# LF3.net
KiCad netlist of a schematic drawn in EasyEDA Pro
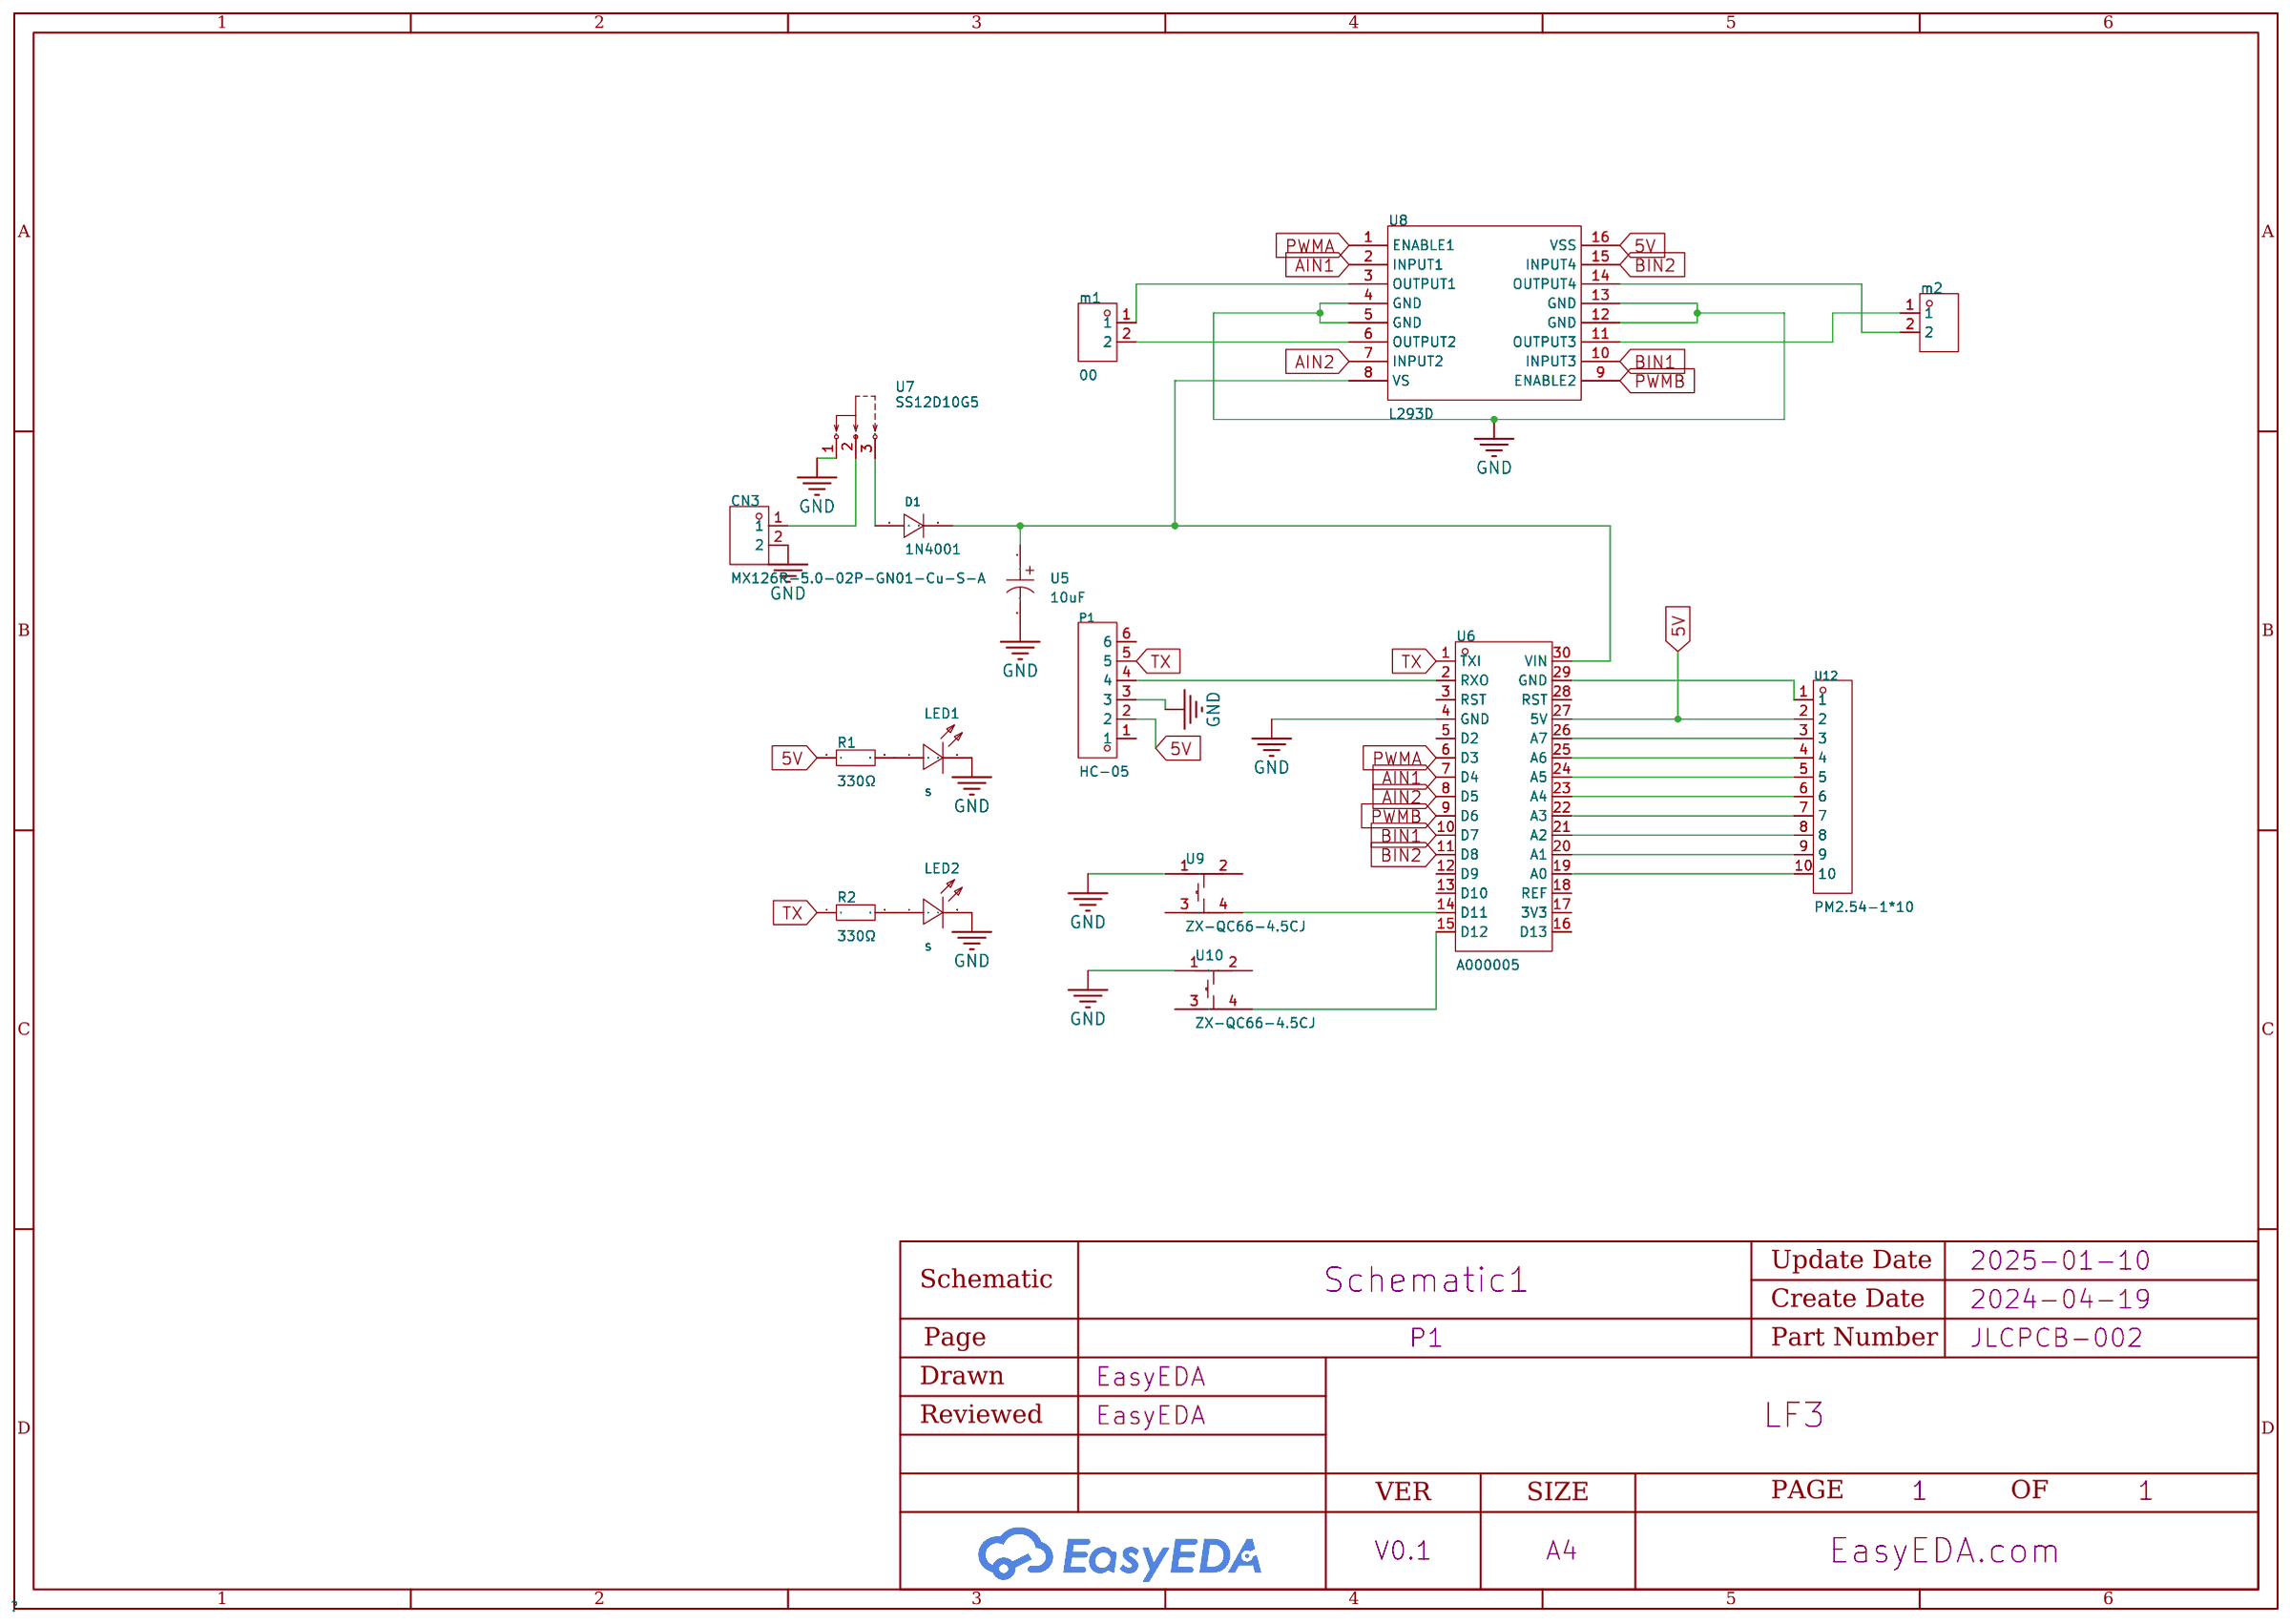
[diagram p0: schematic sheet]

(export (version "E")
  (design (tool "Eeschema 10.0.6"))
  (components
    (comp (ref "CN3")
      (value "MX126R-5.0-02P-GN01-Cu-S-A")
      (footprint "easyedapro:CONN-TH_2P-P5.00-L10.0-W10.3")
      (fields (field (name "Manufacturer") "MAX(迈旭)"))
      (libsource (lib "easyedapro") (part "MX126R-5.0-GN01-2P-CU-S-A"))
    )
    (comp (ref "D1")
      (value "1N4001")
      (footprint "easyedapro:DO-41_BD2.4-L4.7-P8.70-D0.9-RD")
      (fields (field (name "Manufacturer") "DIOFIT(對餘科技)"))
      (libsource (lib "easyedapro") (part "1N4001-C169150"))
    )
    (comp (ref "LED1")
      (value "s")
      (footprint "easyedapro:LED-TH_BD3.8-P2.54-FD")
      (fields (field (name "Manufacturer") "TOGIALED(统佳)"))
      (libsource (lib "easyedapro") (part "TJ-L3FYTLDRMFCSFLC2R-A5"))
    )
    (comp (ref "LED2")
      (value "s")
      (footprint "easyedapro:LED-TH_BD3.8-P2.54-FD")
      (fields (field (name "Manufacturer") "TOGIALED(统佳)"))
      (libsource (lib "easyedapro") (part "TJ-L3FYTLDRMFCSFLC2R-A5"))
    )
    (comp (ref "m1")
      (value "00")
      (footprint "easyedapro:CONN-TH_2P-P5.00-L10.0-W10.3")
      (fields (field (name "Manufacturer") "MAX(迈旭)"))
      (libsource (lib "easyedapro") (part "MX126R-5.0-GN01-2P-CU-S-A"))
    )
    (comp (ref "m2")
      (value "MX126R-5.0-02P-GN01-Cu-S-A")
      (footprint "easyedapro:CONN-TH_2P-P5.00-L10.0-W10.3")
      (fields (field (name "Manufacturer") "MAX(迈旭)"))
      (libsource (lib "easyedapro") (part "MX126R-5.0-GN01-2P-CU-S-A"))
    )
    (comp (ref "P1")
      (value "HC-05")
      (footprint "easyedapro:HDR-TH_6P-P2.54-V-F")
      (fields (field (name "Manufacturer") "BOOMELE(博穆精密)"))
      (libsource (lib "easyedapro") (part "Header-Female-2.54_1x6"))
    )
    (comp (ref "R1")
      (value "330Ω")
      (footprint "easyedapro:RES-TH_BD1.9-L3.3-P7.30-D0.5")
      (fields (field (name "Manufacturer Part") "RN16T25800F") (field (name "Manufacturer") "大毅科技"))
      (libsource (lib "easyedapro") (part "RN16T25800F"))
    )
    (comp (ref "R2")
      (value "330Ω")
      (footprint "easyedapro:RES-TH_BD1.9-L3.3-P7.30-D0.5")
      (fields (field (name "Manufacturer Part") "RN16T25800F") (field (name "Manufacturer") "大毅科技"))
      (libsource (lib "easyedapro") (part "RN16T25800F"))
    )
    (comp (ref "U5")
      (value "10uF")
      (footprint "easyedapro:CAP-TH_BD5.0-P2.00-D0.5-FD")
      (fields (field (name "Manufacturer Part") "152EC0400") (field (name "Manufacturer") "KNSCHA(科尼盛)"))
      (libsource (lib "easyedapro") (part "152EC0400"))
    )
    (comp (ref "U6")
      (value "A000005")
      (footprint "easyedapro:COMM-TH_A000005")
      (fields (field (name "Manufacturer") "arduino"))
      (libsource (lib "easyedapro") (part "A000005"))
    )
    (comp (ref "U7")
      (value "SS12D10G5")
      (footprint "easyedapro:SW-TH_SHOU-HAN_SS12D10G4")
      (fields (field (name "Manufacturer") "SHOU HAN(首韩)"))
      (libsource (lib "easyedapro") (part "SS12D10G5"))
    )
    (comp (ref "U8")
      (value "L293D")
      (footprint "easyedapro:DIP-16_L20.0-W6.4-P2.54-LS7.6-BL")
      (fields (field (name "Manufacturer") "ST(意法半导体)"))
      (libsource (lib "easyedapro") (part "L293D"))
    )
    (comp (ref "U9")
      (value "ZX-QC66-4.5CJ")
      (footprint "easyedapro:KEY-TH_4P-L6.0-W6.0-P4.50-LS6.50")
      (fields (field (name "Manufacturer") "Megastar(兆星)"))
      (libsource (lib "easyedapro") (part "ZX-QC66-4.5CJ"))
    )
    (comp (ref "U10")
      (value "ZX-QC66-4.5CJ")
      (footprint "easyedapro:KEY-TH_4P-L6.0-W6.0-P4.50-LS6.50")
      (fields (field (name "Manufacturer") "Megastar(兆星)"))
      (libsource (lib "easyedapro") (part "ZX-QC66-4.5CJ"))
    )
    (comp (ref "U12")
      (value "PM2.54-1*10")
      (footprint "easyedapro:HDR-TH_10P-P2.54-V-F")
      (fields (field (name "Manufacturer") "ZHOURI(洲日)"))
      (libsource (lib "easyedapro") (part "PM2.54-1*10"))
    )
  )
  (nets
    (net (code "1") (name "5V") (class "Default")
      (node (ref "P1") (pin "2") (pinfunction "2_2") (pintype "input"))
      (node (ref "R1") (pin "1") (pinfunction "1_1") (pintype "unspecified"))
      (node (ref "U12") (pin "2") (pinfunction "2_2") (pintype "input"))
      (node (ref "U6") (pin "27") (pinfunction "5V_27") (pintype "unspecified"))
      (node (ref "U8") (pin "16") (pinfunction "VSS_16") (pintype "unspecified"))
    )
    (net (code "2") (name "AIN1") (class "Default")
      (node (ref "U6") (pin "7") (pinfunction "D4_7") (pintype "unspecified"))
      (node (ref "U8") (pin "2") (pinfunction "INPUT1_2") (pintype "unspecified"))
    )
    (net (code "3") (name "AIN2") (class "Default")
      (node (ref "U6") (pin "8") (pinfunction "D5_8") (pintype "unspecified"))
      (node (ref "U8") (pin "7") (pinfunction "INPUT2_7") (pintype "unspecified"))
    )
    (net (code "4") (name "BIN1") (class "Default")
      (node (ref "U6") (pin "10") (pinfunction "D7_10") (pintype "unspecified"))
      (node (ref "U8") (pin "10") (pinfunction "INPUT3_10") (pintype "unspecified"))
    )
    (net (code "5") (name "BIN2") (class "Default")
      (node (ref "U6") (pin "11") (pinfunction "D8_11") (pintype "unspecified"))
      (node (ref "U8") (pin "15") (pinfunction "INPUT4_15") (pintype "unspecified"))
    )
    (net (code "6") (name "GND") (class "Default")
      (node (ref "CN3") (pin "2") (pinfunction "2_2") (pintype "unspecified"))
      (node (ref "LED1") (pin "2") (pinfunction "K_2") (pintype "unspecified"))
      (node (ref "LED2") (pin "2") (pinfunction "K_2") (pintype "unspecified"))
      (node (ref "P1") (pin "3") (pinfunction "3_3") (pintype "input"))
      (node (ref "U10") (pin "1") (pinfunction "1_1") (pintype "unspecified"))
      (node (ref "U5") (pin "2") (pinfunction "2_2") (pintype "input"))
      (node (ref "U6") (pin "4") (pinfunction "GND_4") (pintype "unspecified"))
      (node (ref "U7") (pin "1") (pinfunction "1_1") (pintype "unspecified"))
      (node (ref "U8") (pin "12") (pinfunction "GND_12") (pintype "unspecified"))
      (node (ref "U8") (pin "13") (pinfunction "GND_13") (pintype "unspecified"))
      (node (ref "U8") (pin "4") (pinfunction "GND_4") (pintype "unspecified"))
      (node (ref "U8") (pin "5") (pinfunction "GND_5") (pintype "unspecified"))
      (node (ref "U9") (pin "1") (pinfunction "1_1") (pintype "unspecified"))
    )
    (net (code "7") (name "Net-(CN3-Pad1)") (class "Default")
      (node (ref "CN3") (pin "1") (pinfunction "1_1") (pintype "unspecified"))
      (node (ref "U7") (pin "2") (pinfunction "2_2") (pintype "unspecified"))
    )
    (net (code "8") (name "Net-(D1-Pad2)") (class "Default")
      (node (ref "D1") (pin "2") (pinfunction "2_2") (pintype "input"))
      (node (ref "U7") (pin "3") (pinfunction "3_3") (pintype "unspecified"))
    )
    (net (code "9") (name "Net-(LED1-A)") (class "Default")
      (node (ref "LED1") (pin "1") (pinfunction "A_1") (pintype "unspecified"))
      (node (ref "R1") (pin "2") (pinfunction "2_2") (pintype "unspecified"))
    )
    (net (code "10") (name "Net-(LED2-A)") (class "Default")
      (node (ref "LED2") (pin "1") (pinfunction "A_1") (pintype "unspecified"))
      (node (ref "R2") (pin "2") (pinfunction "2_2") (pintype "unspecified"))
    )
    (net (code "11") (name "Net-(U6-A0)") (class "Default")
      (node (ref "U12") (pin "10") (pinfunction "10_10") (pintype "input"))
      (node (ref "U6") (pin "19") (pinfunction "A0_19") (pintype "unspecified"))
    )
    (net (code "12") (name "Net-(U6-A1)") (class "Default")
      (node (ref "U12") (pin "9") (pinfunction "9_9") (pintype "input"))
      (node (ref "U6") (pin "20") (pinfunction "A1_20") (pintype "unspecified"))
    )
    (net (code "13") (name "Net-(U6-A2)") (class "Default")
      (node (ref "U12") (pin "8") (pinfunction "8_8") (pintype "input"))
      (node (ref "U6") (pin "21") (pinfunction "A2_21") (pintype "unspecified"))
    )
    (net (code "14") (name "Net-(U6-A3)") (class "Default")
      (node (ref "U12") (pin "7") (pinfunction "7_7") (pintype "input"))
      (node (ref "U6") (pin "22") (pinfunction "A3_22") (pintype "unspecified"))
    )
    (net (code "15") (name "Net-(U6-A4)") (class "Default")
      (node (ref "U12") (pin "6") (pinfunction "6_6") (pintype "input"))
      (node (ref "U6") (pin "23") (pinfunction "A4_23") (pintype "unspecified"))
    )
    (net (code "16") (name "Net-(U6-A5)") (class "Default")
      (node (ref "U12") (pin "5") (pinfunction "5_5") (pintype "input"))
      (node (ref "U6") (pin "24") (pinfunction "A5_24") (pintype "unspecified"))
    )
    (net (code "17") (name "Net-(U6-A6)") (class "Default")
      (node (ref "U12") (pin "4") (pinfunction "4_4") (pintype "input"))
      (node (ref "U6") (pin "25") (pinfunction "A6_25") (pintype "unspecified"))
    )
    (net (code "18") (name "Net-(U6-A7)") (class "Default")
      (node (ref "U12") (pin "3") (pinfunction "3_3") (pintype "input"))
      (node (ref "U6") (pin "26") (pinfunction "A7_26") (pintype "unspecified"))
    )
    (net (code "19") (name "Net-(U6-D11)") (class "Default")
      (node (ref "U6") (pin "14") (pinfunction "D11_14") (pintype "unspecified"))
      (node (ref "U9") (pin "4") (pinfunction "4_4") (pintype "unspecified"))
    )
    (net (code "20") (name "Net-(U6-D12)") (class "Default")
      (node (ref "U10") (pin "4") (pinfunction "4_4") (pintype "unspecified"))
      (node (ref "U6") (pin "15") (pinfunction "D12_15") (pintype "unspecified"))
    )
    (net (code "21") (name "Net-(U6-RXO)") (class "Default")
      (node (ref "P1") (pin "4") (pinfunction "4_4") (pintype "input"))
      (node (ref "U6") (pin "2") (pinfunction "RXO_2") (pintype "unspecified"))
    )
    (net (code "22") (name "Net-(U6-VIN)") (class "Default")
      (node (ref "D1") (pin "1") (pinfunction "1_1") (pintype "input"))
      (node (ref "U5") (pin "1") (pinfunction "1_1") (pintype "input"))
      (node (ref "U6") (pin "30") (pinfunction "VIN_30") (pintype "unspecified"))
      (node (ref "U8") (pin "8") (pinfunction "VS_8") (pintype "unspecified"))
    )
    (net (code "23") (name "Net-(U8-OUTPUT1)") (class "Default")
      (node (ref "U8") (pin "3") (pinfunction "OUTPUT1_3") (pintype "unspecified"))
      (node (ref "m1") (pin "1") (pinfunction "1_1") (pintype "unspecified"))
    )
    (net (code "24") (name "Net-(U8-OUTPUT2)") (class "Default")
      (node (ref "U8") (pin "6") (pinfunction "OUTPUT2_6") (pintype "unspecified"))
      (node (ref "m1") (pin "2") (pinfunction "2_2") (pintype "unspecified"))
    )
    (net (code "25") (name "Net-(U8-OUTPUT3)") (class "Default")
      (node (ref "U8") (pin "11") (pinfunction "OUTPUT3_11") (pintype "unspecified"))
      (node (ref "m2") (pin "1") (pinfunction "1_1") (pintype "unspecified"))
    )
    (net (code "26") (name "Net-(U8-OUTPUT4)") (class "Default")
      (node (ref "U8") (pin "14") (pinfunction "OUTPUT4_14") (pintype "unspecified"))
      (node (ref "m2") (pin "2") (pinfunction "2_2") (pintype "unspecified"))
    )
    (net (code "27") (name "Net-(U12-Pad1)") (class "Default")
      (node (ref "U12") (pin "1") (pinfunction "1_1") (pintype "input"))
      (node (ref "U6") (pin "29") (pinfunction "GND_29") (pintype "unspecified"))
    )
    (net (code "28") (name "PWMA") (class "Default")
      (node (ref "U6") (pin "6") (pinfunction "D3_6") (pintype "unspecified"))
      (node (ref "U8") (pin "1") (pinfunction "ENABLE1_1") (pintype "unspecified"))
    )
    (net (code "29") (name "PWMB") (class "Default")
      (node (ref "U6") (pin "9") (pinfunction "D6_9") (pintype "unspecified"))
      (node (ref "U8") (pin "9") (pinfunction "ENABLE2_9") (pintype "unspecified"))
    )
    (net (code "30") (name "TX") (class "Default")
      (node (ref "P1") (pin "5") (pinfunction "5_5") (pintype "input"))
      (node (ref "R2") (pin "1") (pinfunction "1_1") (pintype "unspecified"))
      (node (ref "U6") (pin "1") (pinfunction "TXI_1") (pintype "unspecified"))
    )
    (net (code "31") (name "unconnected-(P1-Pad1)") (class "Default")
      (node (ref "P1") (pin "1") (pinfunction "1_1") (pintype "input"))
    )
    (net (code "32") (name "unconnected-(P1-Pad6)") (class "Default")
      (node (ref "P1") (pin "6") (pinfunction "6_6") (pintype "input"))
    )
    (net (code "33") (name "unconnected-(U6-3V3-Pad17)") (class "Default")
      (node (ref "U6") (pin "17") (pinfunction "3V3_17") (pintype "unspecified"))
    )
    (net (code "34") (name "unconnected-(U6-D2-Pad5)") (class "Default")
      (node (ref "U6") (pin "5") (pinfunction "D2_5") (pintype "unspecified"))
    )
    (net (code "35") (name "unconnected-(U6-D9-Pad12)") (class "Default")
      (node (ref "U6") (pin "12") (pinfunction "D9_12") (pintype "unspecified"))
    )
    (net (code "36") (name "unconnected-(U6-D10-Pad13)") (class "Default")
      (node (ref "U6") (pin "13") (pinfunction "D10_13") (pintype "unspecified"))
    )
    (net (code "37") (name "unconnected-(U6-D13-Pad16)") (class "Default")
      (node (ref "U6") (pin "16") (pinfunction "D13_16") (pintype "unspecified"))
    )
    (net (code "38") (name "unconnected-(U6-REF-Pad18)") (class "Default")
      (node (ref "U6") (pin "18") (pinfunction "REF_18") (pintype "unspecified"))
    )
    (net (code "39") (name "unconnected-(U6-RST-Pad3)") (class "Default")
      (node (ref "U6") (pin "3") (pinfunction "RST_3") (pintype "unspecified"))
    )
    (net (code "40") (name "unconnected-(U6-RST-Pad28)") (class "Default")
      (node (ref "U6") (pin "28") (pinfunction "RST_28") (pintype "unspecified"))
    )
    (net (code "41") (name "unconnected-(U9-Pad2)") (class "Default")
      (node (ref "U9") (pin "2") (pinfunction "2_2") (pintype "unspecified"))
    )
    (net (code "42") (name "unconnected-(U9-Pad3)") (class "Default")
      (node (ref "U9") (pin "3") (pinfunction "3_3") (pintype "unspecified"))
    )
    (net (code "43") (name "unconnected-(U10-Pad2)") (class "Default")
      (node (ref "U10") (pin "2") (pinfunction "2_2") (pintype "unspecified"))
    )
    (net (code "44") (name "unconnected-(U10-Pad3)") (class "Default")
      (node (ref "U10") (pin "3") (pinfunction "3_3") (pintype "unspecified"))
    )
  )
)
